# Fathom_Drone_Pi_Shield.net
KiCad netlist of a schematic drawn in EAGLE
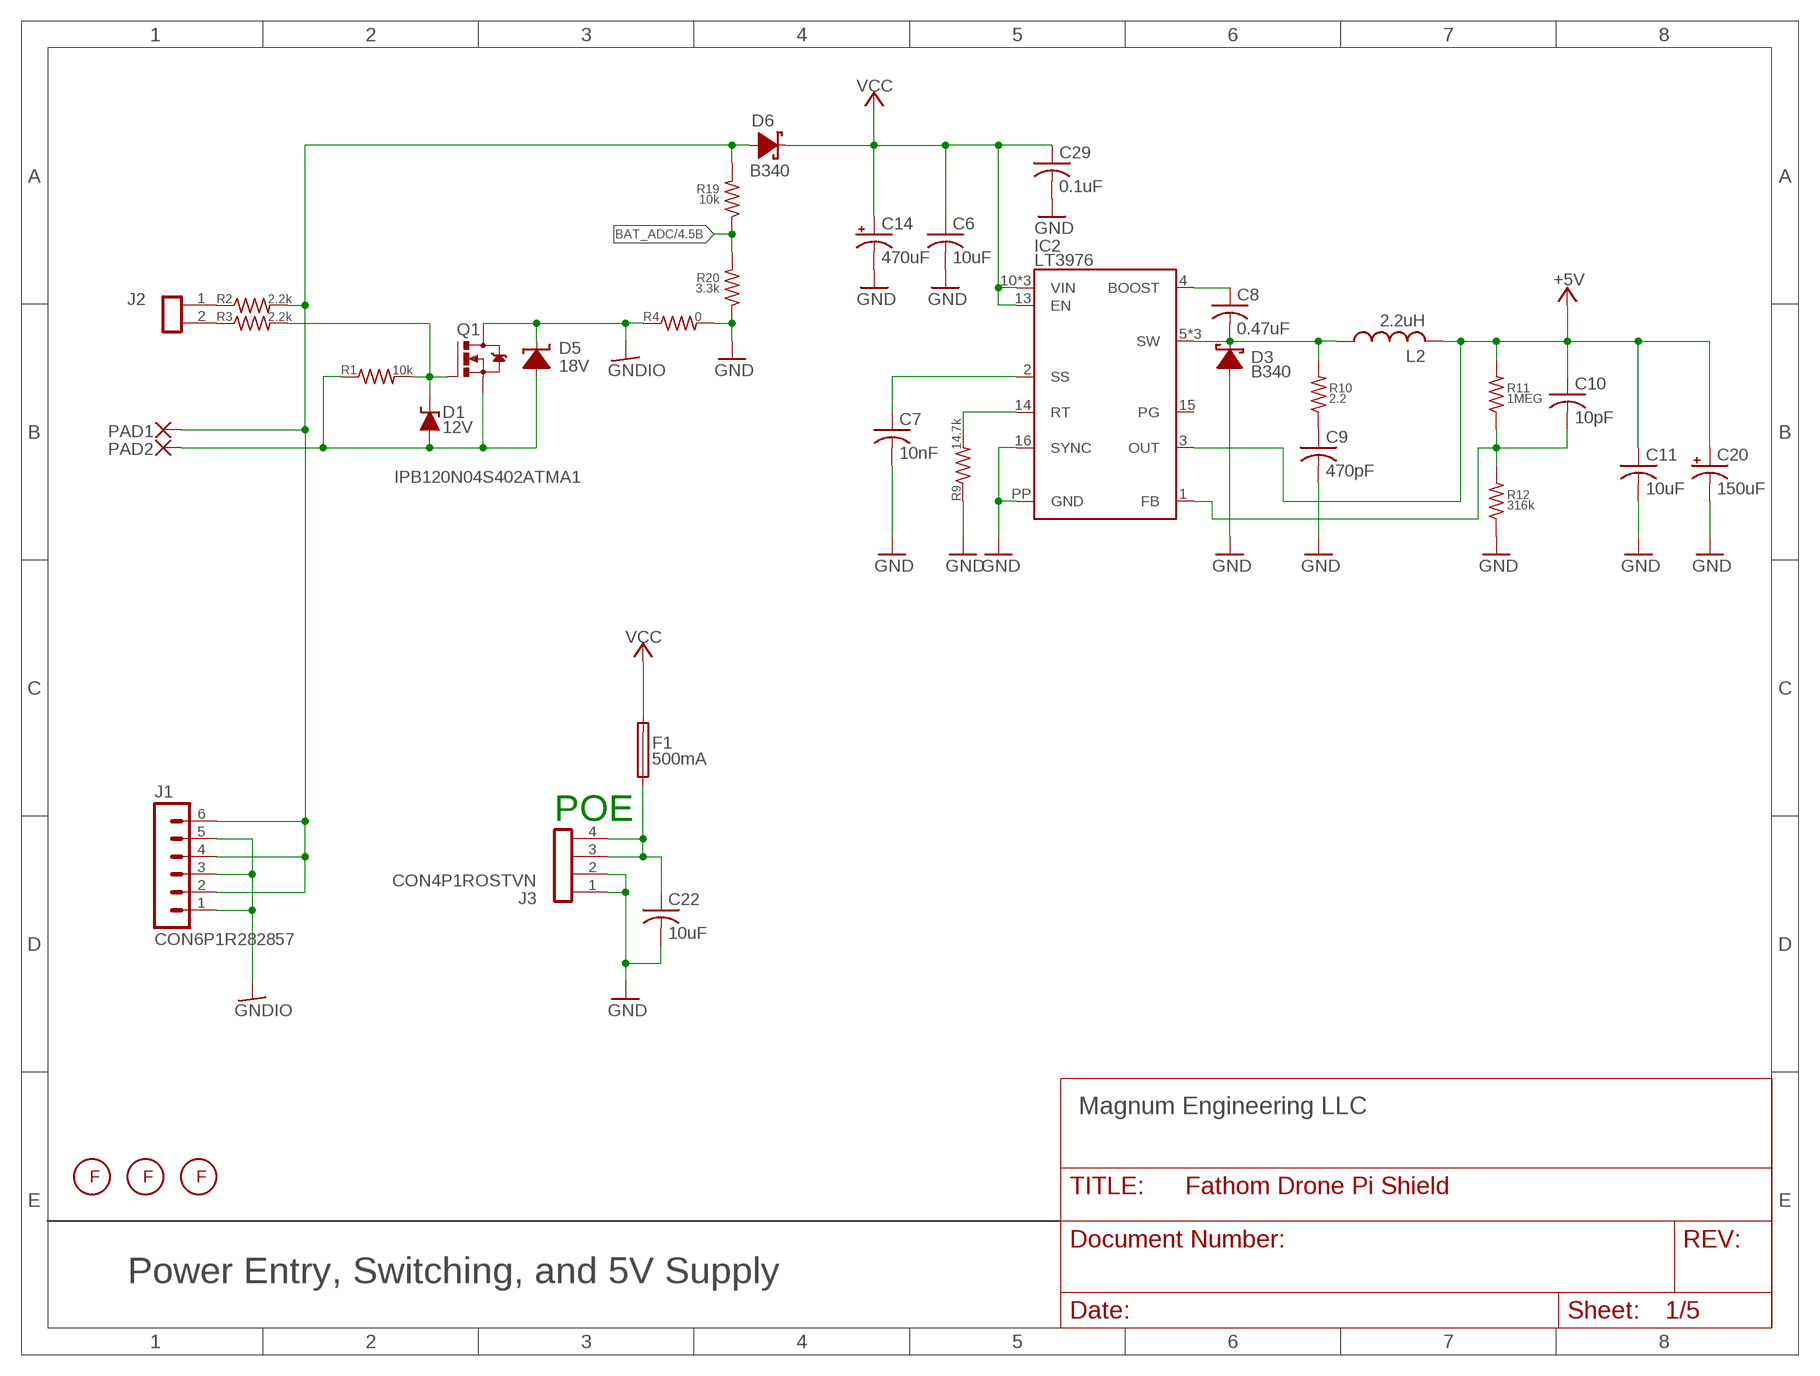
[diagram p0: schematic, sheet 1]
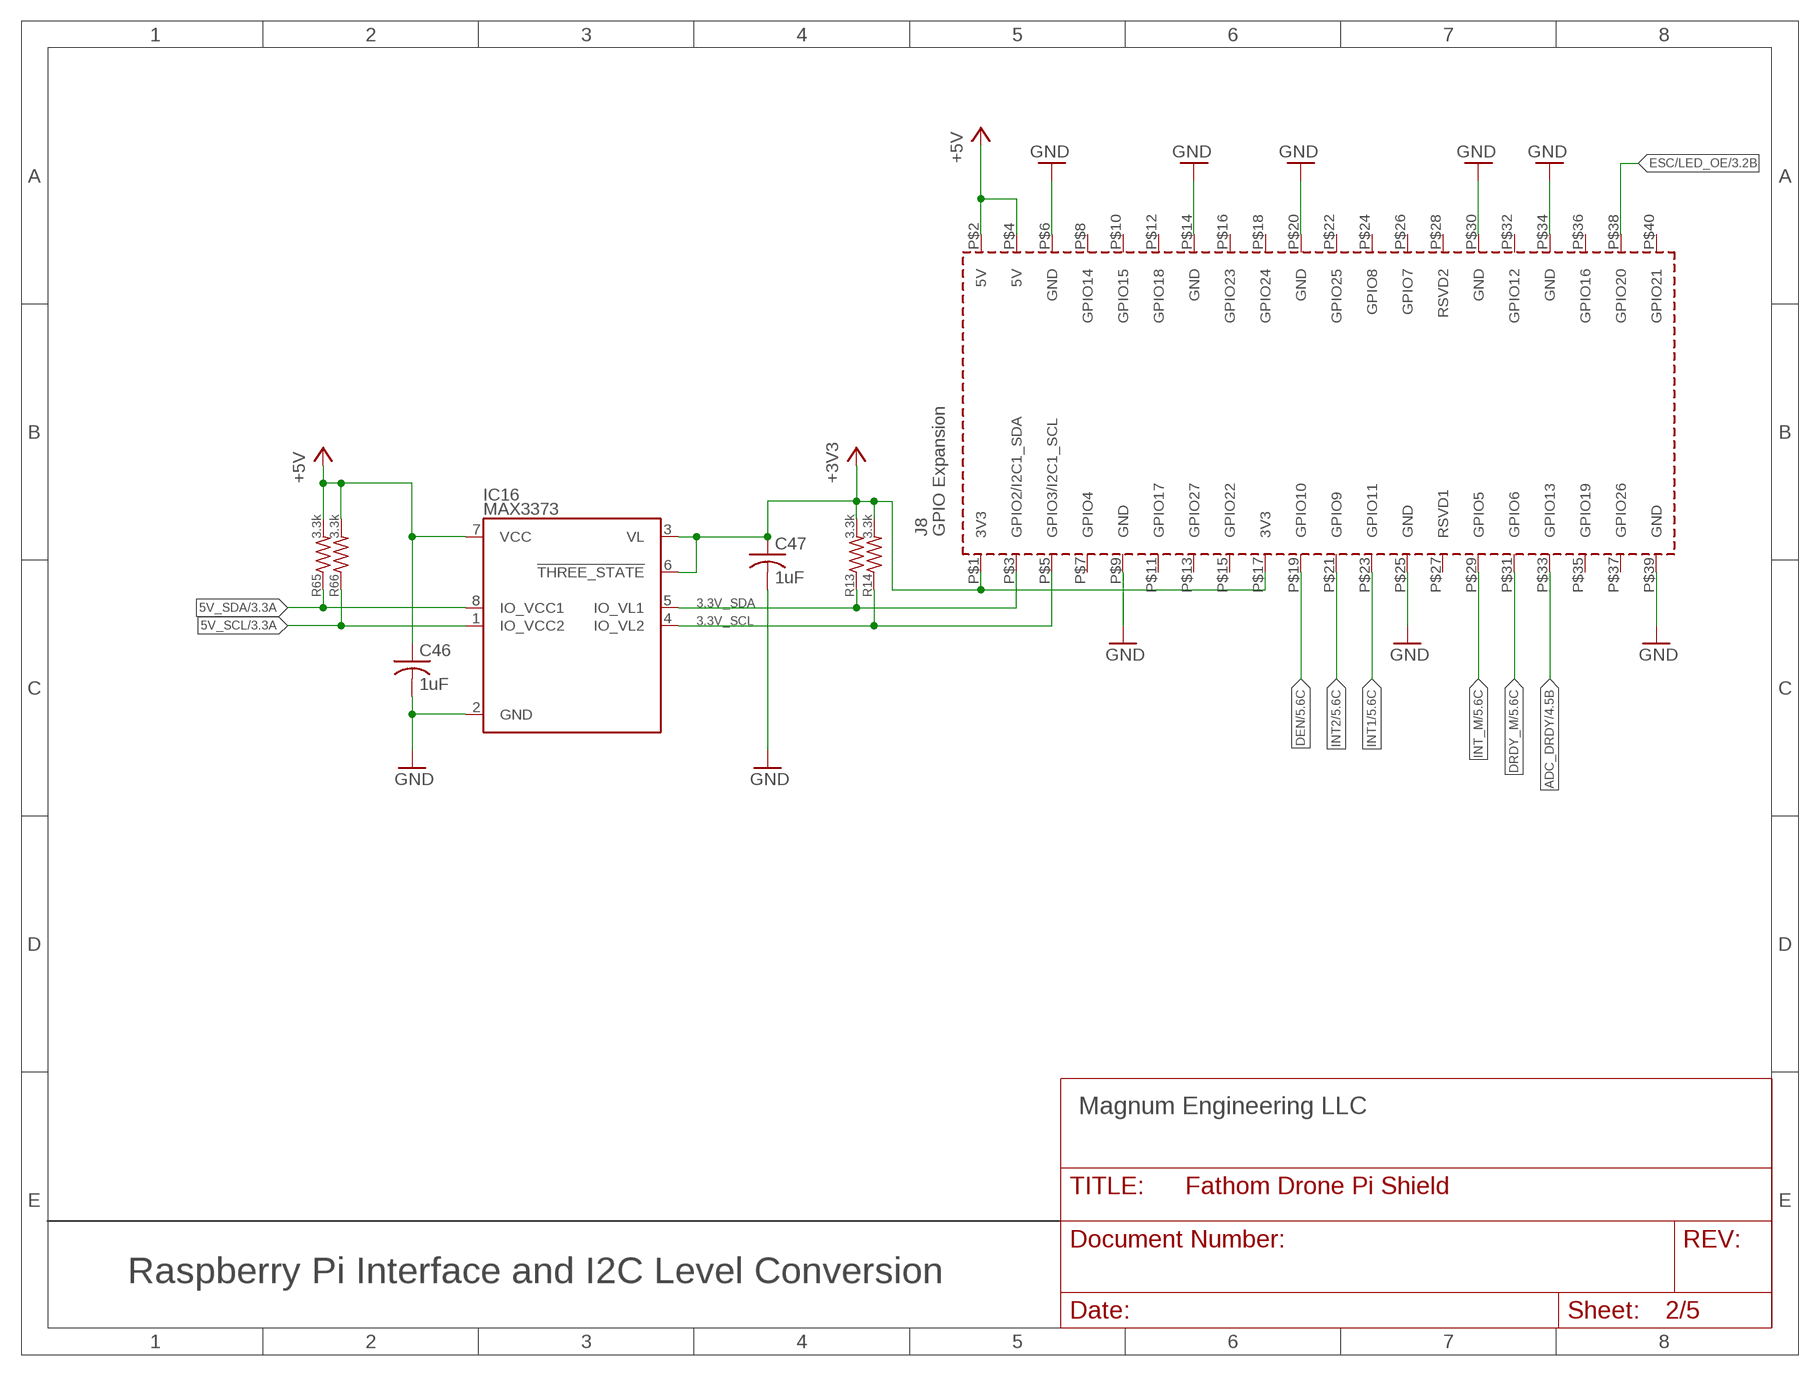
[diagram p1: schematic, sheet 2]
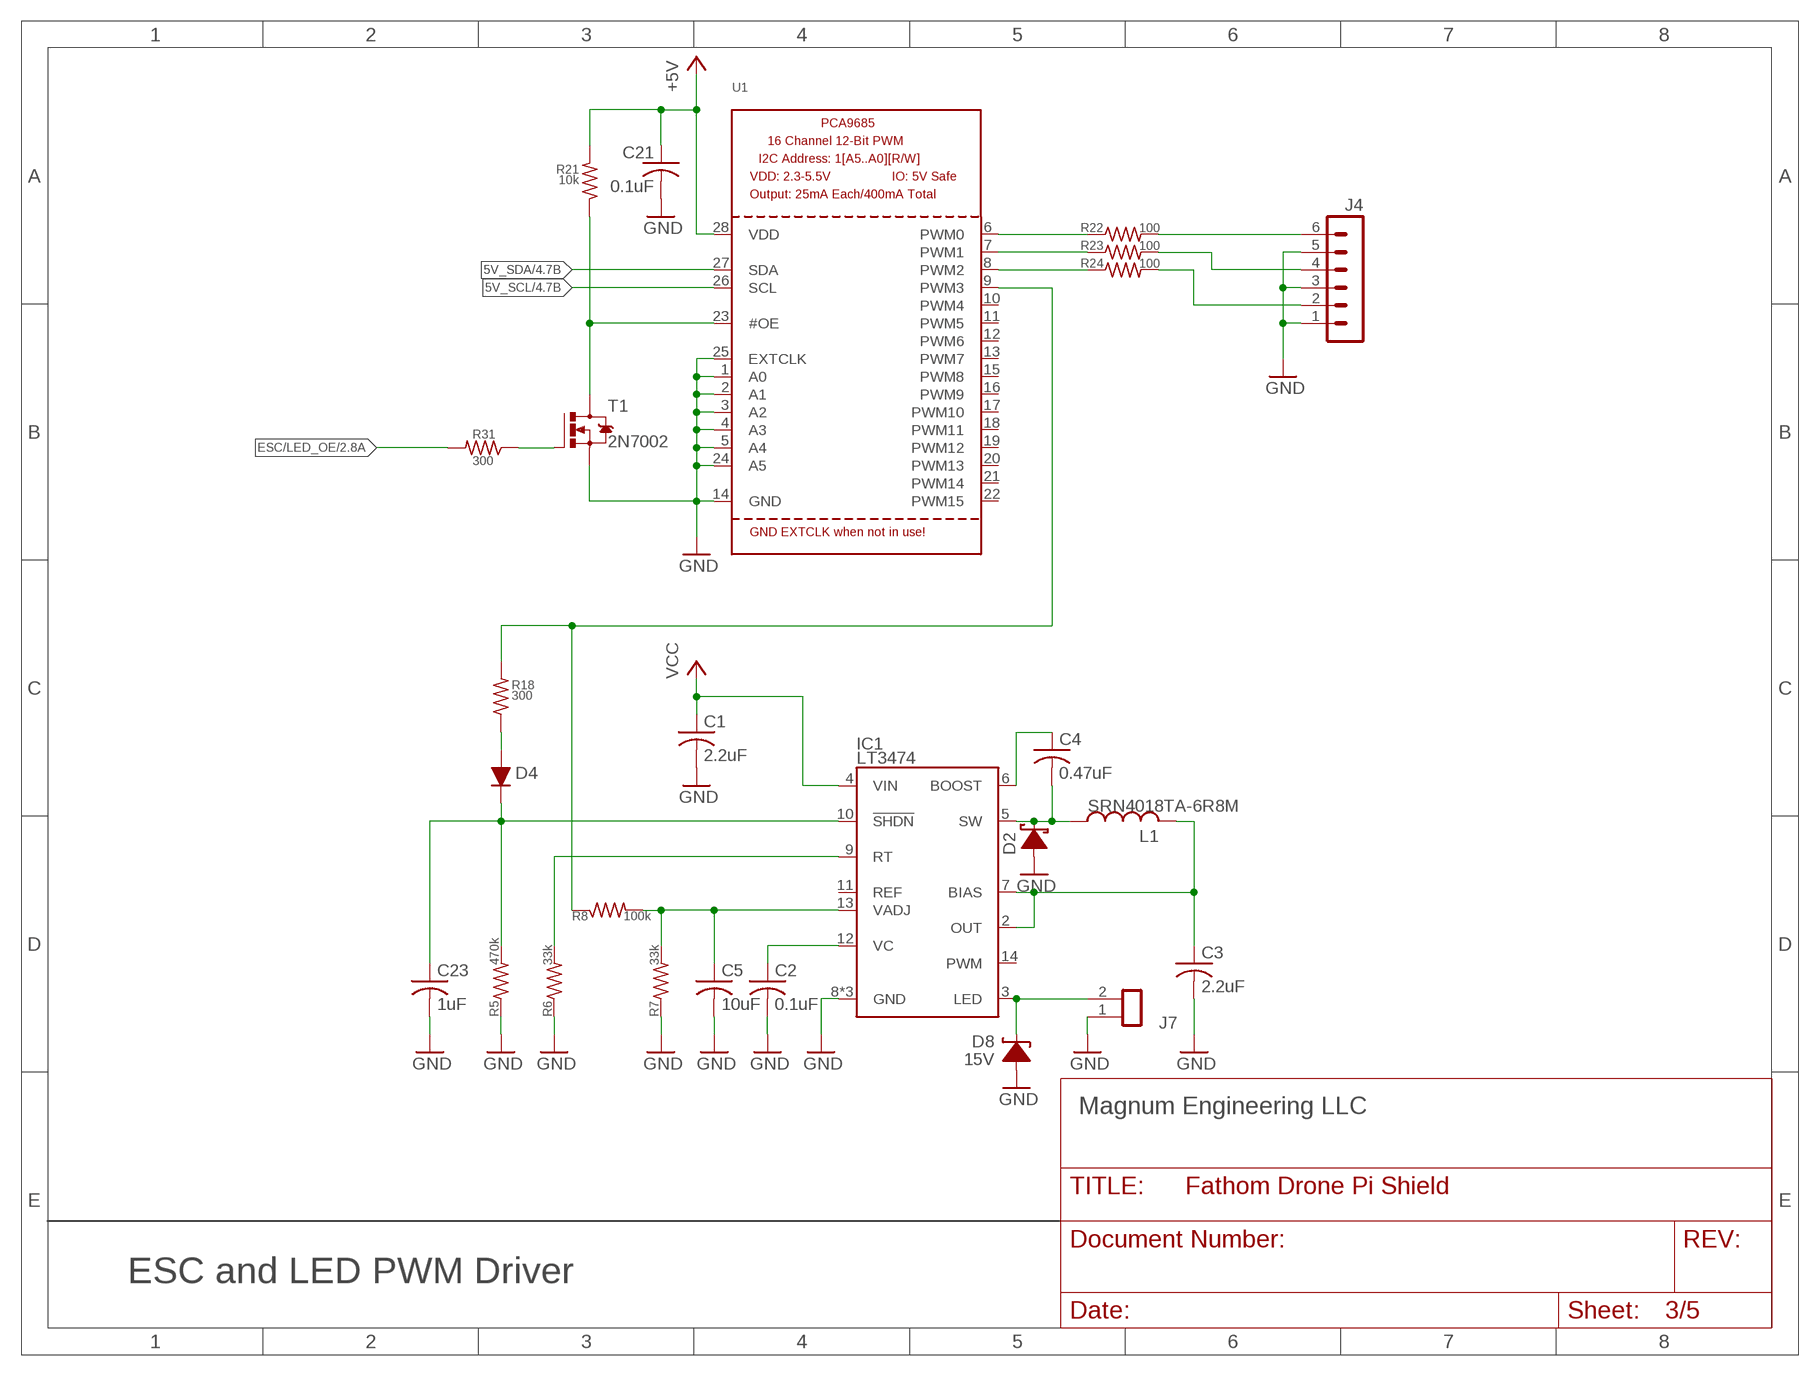
[diagram p2: schematic, sheet 3]
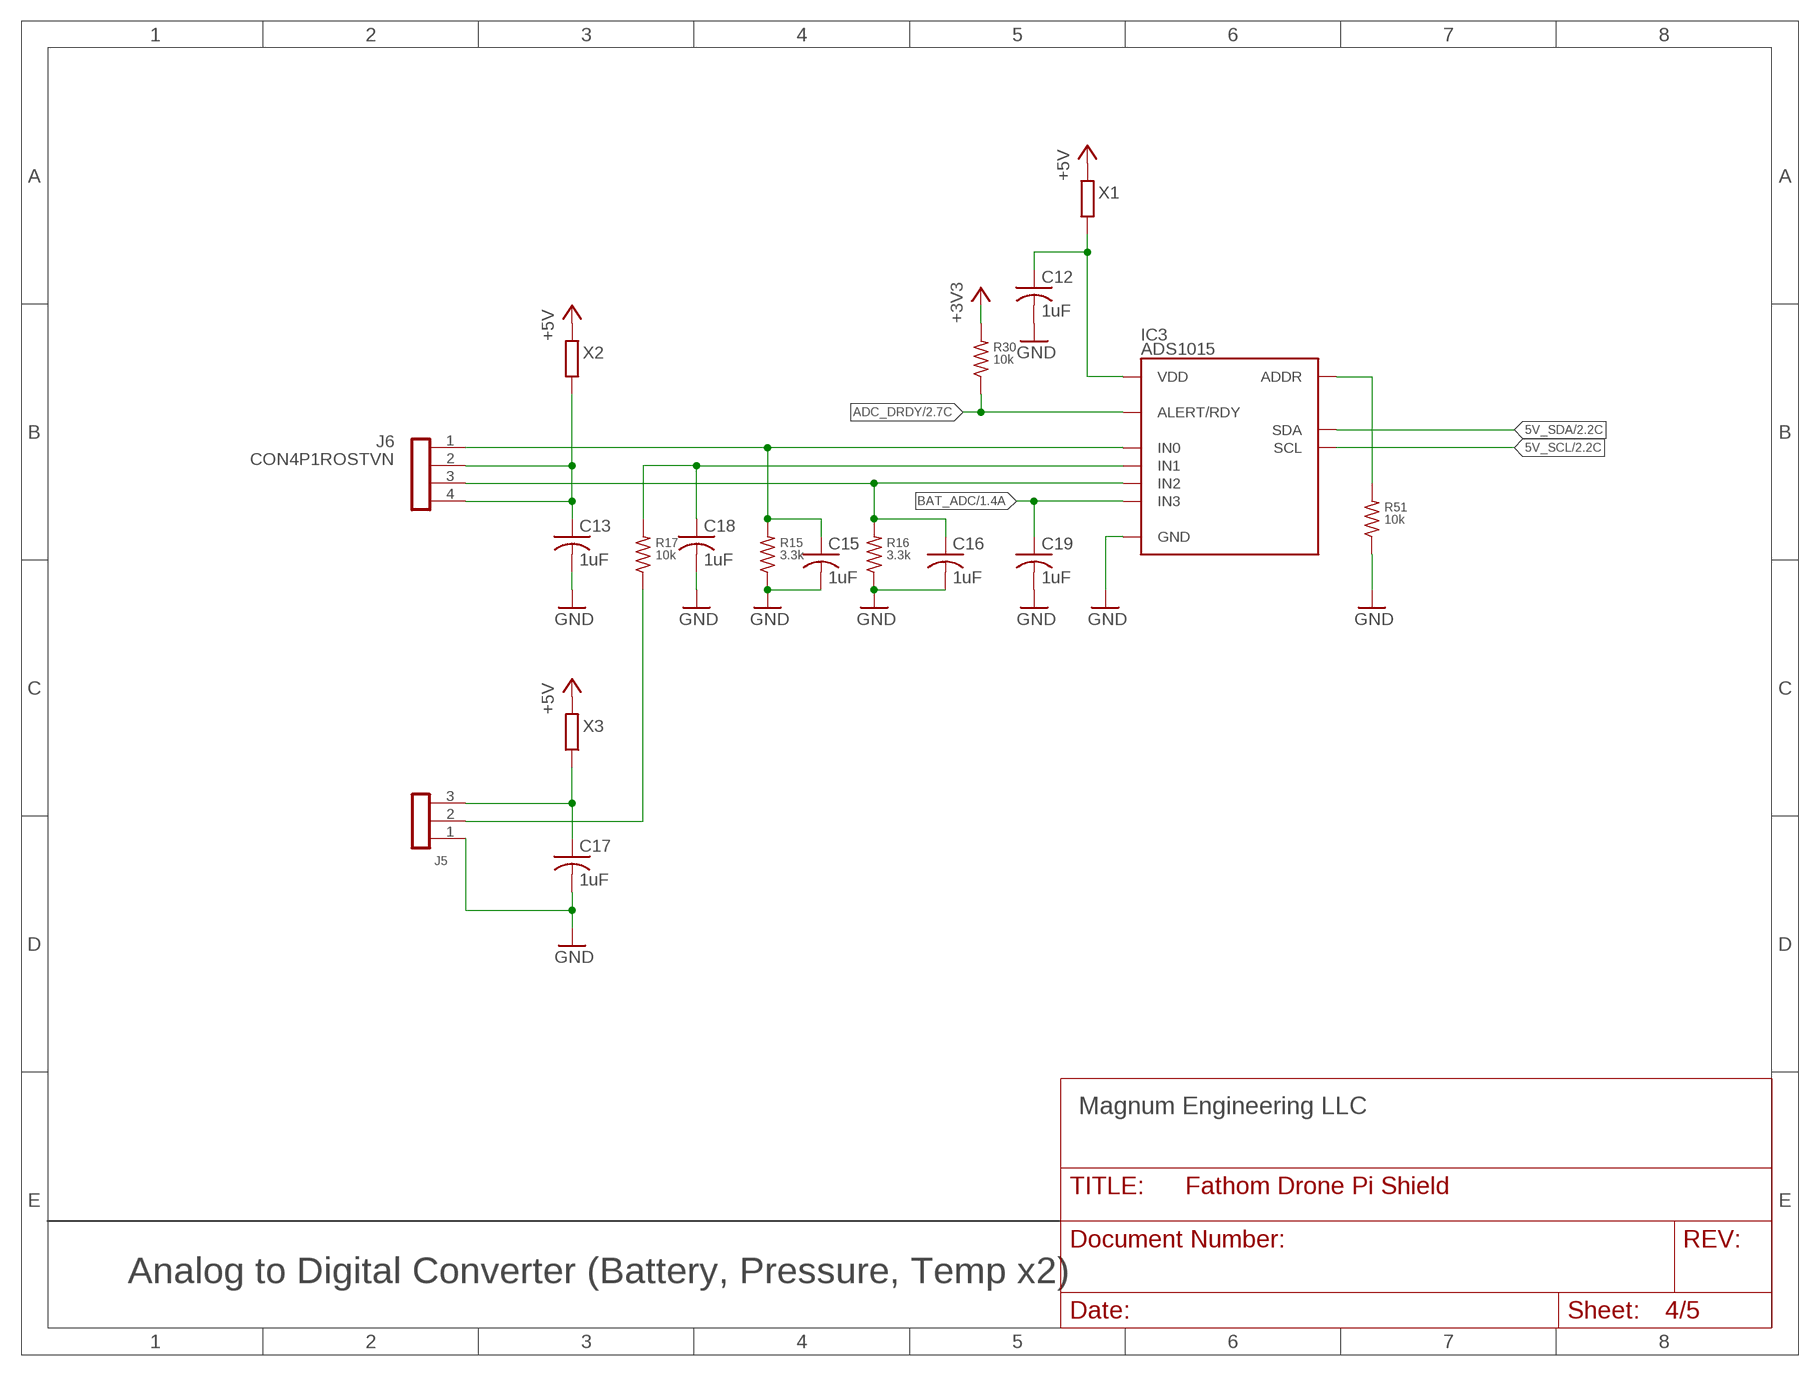
[diagram p3: schematic, sheet 4]
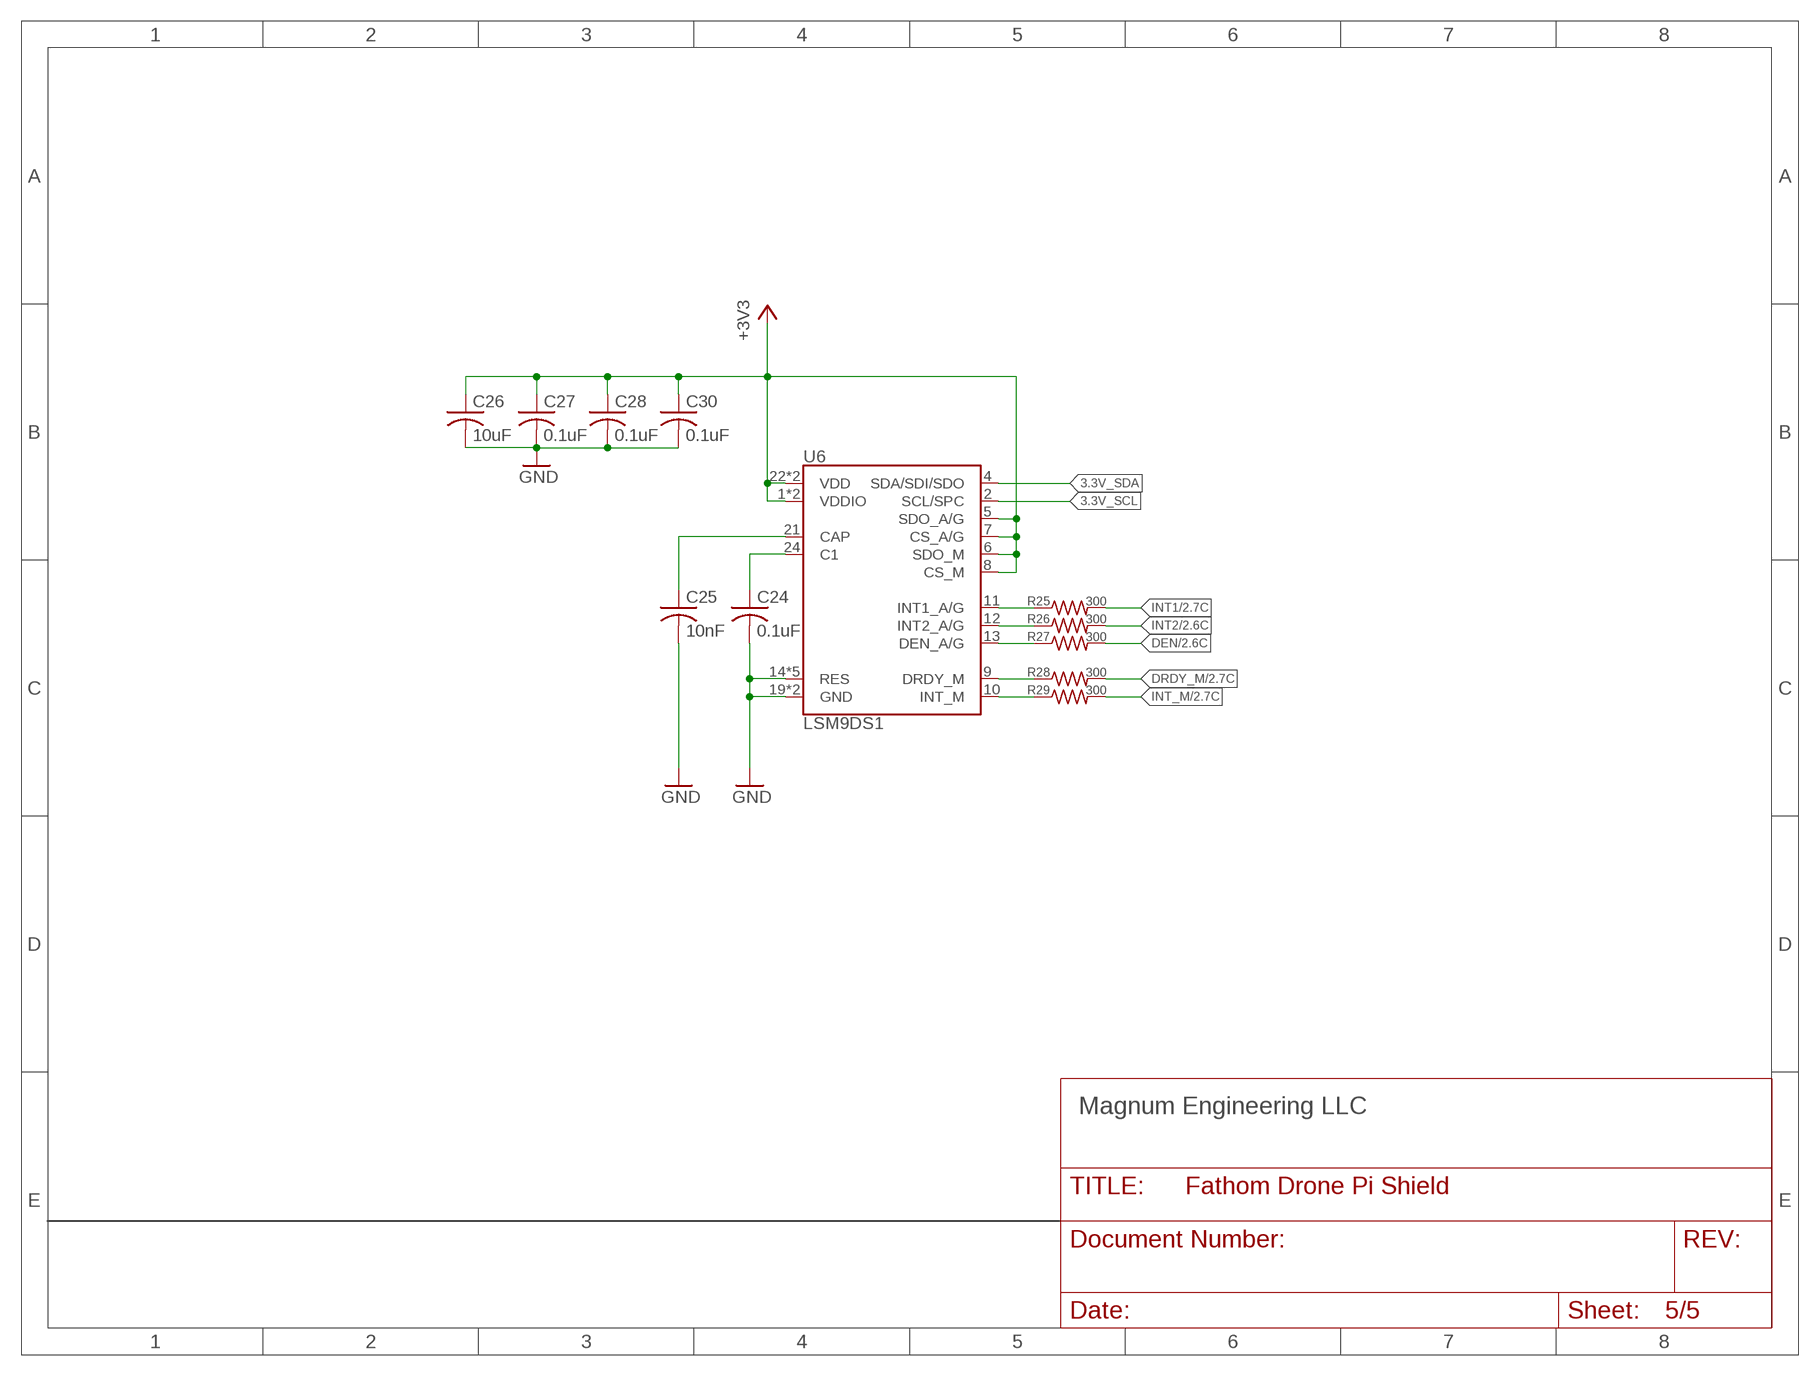
[diagram p4: schematic, sheet 5]

(export (version "E")
  (design (tool "Eeschema 10.0.6"))
  (components
    (comp (ref "C24")
      (value "0.1uF")
      (footprint "eagle-import:C0402")
      (libsource (lib "eagle-import") (part "CAPACITOR0402"))
    )
    (comp (ref "C25")
      (value "10nF")
      (footprint "eagle-import:C0402")
      (libsource (lib "eagle-import") (part "CAPACITOR0402"))
    )
    (comp (ref "C26")
      (value "10uF")
      (footprint "eagle-import:C0805")
      (libsource (lib "eagle-import") (part "CAPACITOR0805"))
    )
    (comp (ref "C27")
      (value "0.1uF")
      (footprint "eagle-import:C0402")
      (libsource (lib "eagle-import") (part "CAPACITOR0402"))
    )
    (comp (ref "C28")
      (value "0.1uF")
      (footprint "eagle-import:C0402")
      (libsource (lib "eagle-import") (part "CAPACITOR0402"))
    )
    (comp (ref "C30")
      (value "0.1uF")
      (footprint "eagle-import:C0402")
      (libsource (lib "eagle-import") (part "CAPACITOR0402"))
    )
    (comp (ref "R25")
      (value "300")
      (footprint "eagle-import:R0402")
      (libsource (lib "eagle-import") (part "RESISTOR0402"))
    )
    (comp (ref "R26")
      (value "300")
      (footprint "eagle-import:R0402")
      (libsource (lib "eagle-import") (part "RESISTOR0402"))
    )
    (comp (ref "R27")
      (value "300")
      (footprint "eagle-import:R0402")
      (libsource (lib "eagle-import") (part "RESISTOR0402"))
    )
    (comp (ref "R28")
      (value "300")
      (footprint "eagle-import:R0402")
      (libsource (lib "eagle-import") (part "RESISTOR0402"))
    )
    (comp (ref "R29")
      (value "300")
      (footprint "eagle-import:R0402")
      (libsource (lib "eagle-import") (part "RESISTOR0402"))
    )
    (comp (ref "U6")
      (value "LSM9DS1")
      (footprint "eagle-import:LGA24-8X4")
      (libsource (lib "eagle-import") (part "LSM9DS1"))
    )
    (comp (ref "C12")
      (value "1uF")
      (footprint "eagle-import:C0402")
      (libsource (lib "eagle-import") (part "CAPACITOR0402"))
    )
    (comp (ref "C13")
      (value "1uF")
      (footprint "eagle-import:C0402")
      (libsource (lib "eagle-import") (part "CAPACITOR0402"))
    )
    (comp (ref "C15")
      (value "1uF")
      (footprint "eagle-import:C0402")
      (libsource (lib "eagle-import") (part "CAPACITOR0402"))
    )
    (comp (ref "C16")
      (value "1uF")
      (footprint "eagle-import:C0402")
      (libsource (lib "eagle-import") (part "CAPACITOR0402"))
    )
    (comp (ref "C17")
      (value "1uF")
      (footprint "eagle-import:C0402")
      (libsource (lib "eagle-import") (part "CAPACITOR0402"))
    )
    (comp (ref "C18")
      (value "1uF")
      (footprint "eagle-import:C0402")
      (libsource (lib "eagle-import") (part "CAPACITOR0402"))
    )
    (comp (ref "C19")
      (value "1uF")
      (footprint "eagle-import:C0402")
      (libsource (lib "eagle-import") (part "CAPACITOR0402"))
    )
    (comp (ref "IC3")
      (value "ADS1015")
      (footprint "eagle-import:MSOP10")
      (libsource (lib "eagle-import") (part "ADS1015"))
    )
    (comp (ref "J5")
      (value "CON3P1ROSTVN")
      (footprint "eagle-import:OSTVN03A150")
      (libsource (lib "eagle-import") (part "CON3P1ROSTVN"))
    )
    (comp (ref "J6")
      (value "CON4P1ROSTVN")
      (footprint "eagle-import:OSTVN04A150")
      (libsource (lib "eagle-import") (part "CON4P1ROSTVN"))
    )
    (comp (ref "R15")
      (value "3.3k")
      (footprint "eagle-import:R0402")
      (libsource (lib "eagle-import") (part "RESISTOR0402"))
    )
    (comp (ref "R16")
      (value "3.3k")
      (footprint "eagle-import:R0402")
      (libsource (lib "eagle-import") (part "RESISTOR0402"))
    )
    (comp (ref "R17")
      (value "10k")
      (footprint "eagle-import:R0603")
      (libsource (lib "eagle-import") (part "RESISTOR0603"))
    )
    (comp (ref "R30")
      (value "10k")
      (footprint "eagle-import:R0603")
      (libsource (lib "eagle-import") (part "RESISTOR0603"))
    )
    (comp (ref "R51")
      (value "10k")
      (footprint "eagle-import:R0603")
      (libsource (lib "eagle-import") (part "RESISTOR0603"))
    )
    (comp (ref "X1")
      (value "PASSIVE0603")
      (footprint "eagle-import:R0603@1")
      (libsource (lib "eagle-import") (part "PASSIVE0603"))
    )
    (comp (ref "X2")
      (value "PASSIVE0603")
      (footprint "eagle-import:R0603@1")
      (libsource (lib "eagle-import") (part "PASSIVE0603"))
    )
    (comp (ref "X3")
      (value "PASSIVE0603")
      (footprint "eagle-import:R0603@1")
      (libsource (lib "eagle-import") (part "PASSIVE0603"))
    )
    (comp (ref "C46")
      (value "1uF")
      (footprint "eagle-import:C0402")
      (libsource (lib "eagle-import") (part "CAPACITOR0402"))
    )
    (comp (ref "C47")
      (value "1uF")
      (footprint "eagle-import:C0402")
      (libsource (lib "eagle-import") (part "CAPACITOR0402"))
    )
    (comp (ref "IC16")
      (value "MAX3373")
      (footprint "eagle-import:TS8")
      (libsource (lib "eagle-import") (part "MAX3373"))
    )
    (comp (ref "PCB1")
      (value "RPI3")
      (footprint "eagle-import:RPI3")
      (libsource (lib "eagle-import") (part "RPI3"))
    )
    (comp (ref "R13")
      (value "3.3k")
      (footprint "eagle-import:R0402")
      (libsource (lib "eagle-import") (part "RESISTOR0402"))
    )
    (comp (ref "R14")
      (value "3.3k")
      (footprint "eagle-import:R0402")
      (libsource (lib "eagle-import") (part "RESISTOR0402"))
    )
    (comp (ref "R65")
      (value "3.3k")
      (footprint "eagle-import:R0402")
      (libsource (lib "eagle-import") (part "RESISTOR0402"))
    )
    (comp (ref "R66")
      (value "3.3k")
      (footprint "eagle-import:R0402")
      (libsource (lib "eagle-import") (part "RESISTOR0402"))
    )
    (comp (ref "C6")
      (value "10uF")
      (footprint "eagle-import:C1206")
      (libsource (lib "eagle-import") (part "C-USC1206"))
    )
    (comp (ref "C7")
      (value "10nF")
      (footprint "eagle-import:C0402")
      (libsource (lib "eagle-import") (part "CAPACITOR0402"))
    )
    (comp (ref "C8")
      (value "0.47uF")
      (footprint "eagle-import:C0603")
      (libsource (lib "eagle-import") (part "CAPACITOR0603"))
    )
    (comp (ref "C9")
      (value "470pF")
      (footprint "eagle-import:C0603")
      (libsource (lib "eagle-import") (part "CAPACITOR0603"))
    )
    (comp (ref "C10")
      (value "10pF")
      (footprint "eagle-import:C0603")
      (libsource (lib "eagle-import") (part "CAPACITOR0603"))
    )
    (comp (ref "C11")
      (value "10uF")
      (footprint "eagle-import:C0805")
      (libsource (lib "eagle-import") (part "CAPACITOR0805"))
    )
    (comp (ref "C14")
      (value "470uF")
      (footprint "eagle-import:E3,5-8")
      (libsource (lib "eagle-import") (part "CPOL-USE3.5-8"))
    )
    (comp (ref "C20")
      (value "150uF")
      (footprint "eagle-import:PANASONIC_C")
      (libsource (lib "eagle-import") (part "CPOL-USC"))
    )
    (comp (ref "C22")
      (value "10uF")
      (footprint "eagle-import:C1206")
      (libsource (lib "eagle-import") (part "C-USC1206"))
    )
    (comp (ref "C29")
      (value "0.1uF")
      (footprint "eagle-import:C0402")
      (libsource (lib "eagle-import") (part "C-USC0402"))
    )
    (comp (ref "D1")
      (value "12V")
      (footprint "eagle-import:SOT-23")
      (libsource (lib "eagle-import") (part "ZENERSOT-23"))
    )
    (comp (ref "D3")
      (value "B340")
      (footprint "eagle-import:SMA")
      (libsource (lib "eagle-import") (part "DIODE-SCHOTTKYSMA"))
    )
    (comp (ref "D5")
      (value "18V")
      (footprint "eagle-import:SMC")
      (libsource (lib "eagle-import") (part "TVSSMC"))
    )
    (comp (ref "D6")
      (value "B340")
      (footprint "eagle-import:SMA")
      (libsource (lib "eagle-import") (part "DIODE-SCHOTTKYSMA"))
    )
    (comp (ref "F1")
      (value "500mA")
      (footprint "eagle-import:BETTER_LITTELFUSE1812")
      (libsource (lib "eagle-import") (part "FUSEBETTER_1812"))
    )
    (comp (ref "FM1")
      (value "FIDUCIAL1MM")
      (footprint "eagle-import:1MMCIRCLE")
      (libsource (lib "eagle-import") (part "FIDUCIAL1MM"))
    )
    (comp (ref "FM2")
      (value "FIDUCIAL1MM")
      (footprint "eagle-import:1MMCIRCLE")
      (libsource (lib "eagle-import") (part "FIDUCIAL1MM"))
    )
    (comp (ref "FM3")
      (value "FIDUCIAL1MM")
      (footprint "eagle-import:1MMCIRCLE")
      (libsource (lib "eagle-import") (part "FIDUCIAL1MM"))
    )
    (comp (ref "IC2")
      (value "LT3976")
      (footprint "eagle-import:MSOP-16-PP")
      (libsource (lib "eagle-import") (part "LT3976"))
    )
    (comp (ref "J1")
      (value "CON6P1R282857")
      (footprint "eagle-import:282857-6")
      (libsource (lib "eagle-import") (part "CON6P1R282857"))
    )
    (comp (ref "J2")
      (value "CON2P1ROSTVN")
      (footprint "eagle-import:OSTVN02A150")
      (libsource (lib "eagle-import") (part "CON2P1ROSTVN"))
    )
    (comp (ref "J3")
      (value "CON4P1ROSTVN")
      (footprint "eagle-import:OSTVN04A150")
      (libsource (lib "eagle-import") (part "CON4P1ROSTVN"))
    )
    (comp (ref "L2")
      (value "2.2uH")
      (footprint "eagle-import:VLP8040")
      (libsource (lib "eagle-import") (part "L-USVLP8040"))
    )
    (comp (ref "PAD1")
      (value "WIREPAD5.5/3,0")
      (footprint "eagle-import:5.5_3,0")
      (libsource (lib "eagle-import") (part "WIREPAD5.5/3,0"))
    )
    (comp (ref "PAD2")
      (value "WIREPAD5.5/3,0")
      (footprint "eagle-import:5.5_3,0")
      (libsource (lib "eagle-import") (part "WIREPAD5.5/3,0"))
    )
    (comp (ref "Q1")
      (value "IPB120N04S402ATMA1")
      (footprint "eagle-import:TO263")
      (libsource (lib "eagle-import") (part "MOSFET-NTO263"))
    )
    (comp (ref "R1")
      (value "10k")
      (footprint "eagle-import:R0603")
      (libsource (lib "eagle-import") (part "RESISTOR0603"))
    )
    (comp (ref "R2")
      (value "2.2k")
      (footprint "eagle-import:R0603")
      (libsource (lib "eagle-import") (part "RESISTOR0603"))
    )
    (comp (ref "R3")
      (value "2.2k")
      (footprint "eagle-import:R0603")
      (libsource (lib "eagle-import") (part "RESISTOR0603"))
    )
    (comp (ref "R4")
      (value "0")
      (footprint "eagle-import:R0805")
      (libsource (lib "eagle-import") (part "RESISTOR0805"))
    )
    (comp (ref "R9")
      (value "14.7k")
      (footprint "eagle-import:R0603")
      (libsource (lib "eagle-import") (part "RESISTOR0603"))
    )
    (comp (ref "R10")
      (value "2.2")
      (footprint "eagle-import:R0603")
      (libsource (lib "eagle-import") (part "RESISTOR0603"))
    )
    (comp (ref "R11")
      (value "1MEG")
      (footprint "eagle-import:R0603")
      (libsource (lib "eagle-import") (part "RESISTOR0603"))
    )
    (comp (ref "R12")
      (value "316k")
      (footprint "eagle-import:R0603")
      (libsource (lib "eagle-import") (part "RESISTOR0603"))
    )
    (comp (ref "R19")
      (value "10k")
      (footprint "eagle-import:R0603")
      (libsource (lib "eagle-import") (part "RESISTOR0603"))
    )
    (comp (ref "R20")
      (value "3.3k")
      (footprint "eagle-import:R0402")
      (libsource (lib "eagle-import") (part "RESISTOR0402"))
    )
    (comp (ref "C1")
      (value "2.2uF")
      (footprint "eagle-import:C0603")
      (libsource (lib "eagle-import") (part "CAPACITOR0603"))
    )
    (comp (ref "C2")
      (value "0.1uF")
      (footprint "eagle-import:C0402")
      (libsource (lib "eagle-import") (part "CAPACITOR0402"))
    )
    (comp (ref "C3")
      (value "2.2uF")
      (footprint "eagle-import:C0603")
      (libsource (lib "eagle-import") (part "CAPACITOR0603"))
    )
    (comp (ref "C4")
      (value "0.47uF")
      (footprint "eagle-import:C0603")
      (libsource (lib "eagle-import") (part "CAPACITOR0603"))
    )
    (comp (ref "C5")
      (value "10uF")
      (footprint "eagle-import:C0805")
      (libsource (lib "eagle-import") (part "CAPACITOR0805"))
    )
    (comp (ref "C21")
      (value "0.1uF")
      (footprint "eagle-import:C0402")
      (libsource (lib "eagle-import") (part "CAPACITOR0402"))
    )
    (comp (ref "C23")
      (value "1uF")
      (footprint "eagle-import:C0402")
      (libsource (lib "eagle-import") (part "CAPACITOR0402"))
    )
    (comp (ref "D2")
      (value "DIODE-SCHOTTKYSMA")
      (footprint "eagle-import:SMA")
      (libsource (lib "eagle-import") (part "DIODE-SCHOTTKYSMA"))
    )
    (comp (ref "D4")
      (value "DIODESOD-123")
      (footprint "eagle-import:SOD-123")
      (libsource (lib "eagle-import") (part "DIODESOD-123"))
    )
    (comp (ref "D8")
      (value "15V")
      (footprint "eagle-import:SOD123FL")
      (libsource (lib "eagle-import") (part "TVSSOD123FL"))
    )
    (comp (ref "IC1")
      (value "LT3474")
      (footprint "eagle-import:TSSOP16_PP")
      (libsource (lib "eagle-import") (part "LT3474"))
    )
    (comp (ref "J4")
      (value "CON6P1ROSTVN")
      (footprint "eagle-import:OSTVN06A150")
      (libsource (lib "eagle-import") (part "CON6P1ROSTVN"))
    )
    (comp (ref "J7")
      (value "CON2P1ROSTVN")
      (footprint "eagle-import:OSTVN02A150")
      (libsource (lib "eagle-import") (part "CON2P1ROSTVN"))
    )
    (comp (ref "L1")
      (value "SRN4018TA-6R8M")
      (footprint "eagle-import:L-4026")
      (libsource (lib "eagle-import") (part "L-US4026"))
    )
    (comp (ref "R5")
      (value "470k")
      (footprint "eagle-import:R0603")
      (libsource (lib "eagle-import") (part "RESISTOR0603"))
    )
    (comp (ref "R6")
      (value "33k")
      (footprint "eagle-import:R0603")
      (libsource (lib "eagle-import") (part "RESISTOR0603"))
    )
    (comp (ref "R7")
      (value "33k")
      (footprint "eagle-import:R0603")
      (libsource (lib "eagle-import") (part "RESISTOR0603"))
    )
    (comp (ref "R8")
      (value "100k")
      (footprint "eagle-import:R0603")
      (libsource (lib "eagle-import") (part "RESISTOR0603"))
    )
    (comp (ref "R18")
      (value "300")
      (footprint "eagle-import:R0402")
      (libsource (lib "eagle-import") (part "RESISTOR0402"))
    )
    (comp (ref "R21")
      (value "10k")
      (footprint "eagle-import:R0603")
      (libsource (lib "eagle-import") (part "RESISTOR0603"))
    )
    (comp (ref "R22")
      (value "100")
      (footprint "eagle-import:R0603")
      (libsource (lib "eagle-import") (part "RESISTOR0603"))
    )
    (comp (ref "R23")
      (value "100")
      (footprint "eagle-import:R0603")
      (libsource (lib "eagle-import") (part "RESISTOR0603"))
    )
    (comp (ref "R24")
      (value "100")
      (footprint "eagle-import:R0603")
      (libsource (lib "eagle-import") (part "RESISTOR0603"))
    )
    (comp (ref "R31")
      (value "300")
      (footprint "eagle-import:R0402")
      (libsource (lib "eagle-import") (part "RESISTOR0402"))
    )
    (comp (ref "T1")
      (value "2N7002")
      (footprint "eagle-import:SOT-23")
      (libsource (lib "eagle-import") (part "N-MOSFET"))
    )
    (comp (ref "U1")
      (value "PCA9685")
      (footprint "eagle-import:TSSOP28")
      (libsource (lib "eagle-import") (part "PCA9685"))
    )
  )
  (nets
    (net (code "1") (name "+3V3") (class "Default")
      (node (ref "C26") (pin "1") (pinfunction "1_1") (pintype "passive"))
      (node (ref "C27") (pin "1") (pinfunction "1_1") (pintype "passive"))
      (node (ref "C28") (pin "1") (pinfunction "1_1") (pintype "passive"))
      (node (ref "C30") (pin "1") (pinfunction "1_1") (pintype "passive"))
      (node (ref "C47") (pin "1") (pinfunction "1_1") (pintype "passive"))
      (node (ref "IC16") (pin "3") (pinfunction "VL_3") (pintype "power_in"))
      (node (ref "IC16") (pin "6") (pinfunction "~{THREE_STATE}_6") (pintype "input"))
      (node (ref "PCB1") (pin "P$1") (pinfunction "3V3_P$1") (pintype "bidirectional"))
      (node (ref "PCB1") (pin "P$17") (pinfunction "3V3_P$17") (pintype "bidirectional"))
      (node (ref "R13") (pin "2") (pinfunction "2_2") (pintype "passive"))
      (node (ref "R14") (pin "2") (pinfunction "2_2") (pintype "passive"))
      (node (ref "R30") (pin "2") (pinfunction "2_2") (pintype "passive"))
      (node (ref "U6") (pin "1") (pinfunction "VDDIO_1") (pintype "bidirectional"))
      (node (ref "U6") (pin "22") (pinfunction "VDD_22") (pintype "bidirectional"))
      (node (ref "U6") (pin "23") (pinfunction "VDD_23") (pintype "bidirectional"))
      (node (ref "U6") (pin "3") (pinfunction "VDDIO_3") (pintype "bidirectional"))
      (node (ref "U6") (pin "5") (pinfunction "SDO_A/G_5") (pintype "bidirectional"))
      (node (ref "U6") (pin "6") (pinfunction "SDO_M_6") (pintype "bidirectional"))
      (node (ref "U6") (pin "7") (pinfunction "CS_A/G_7") (pintype "bidirectional"))
      (node (ref "U6") (pin "8") (pinfunction "CS_M_8") (pintype "bidirectional"))
    )
    (net (code "2") (name "+5V") (class "Default")
      (node (ref "C10") (pin "1") (pinfunction "1_1") (pintype "passive"))
      (node (ref "C11") (pin "1") (pinfunction "1_1") (pintype "passive"))
      (node (ref "C20") (pin "+") (pinfunction "+_+") (pintype "passive"))
      (node (ref "C21") (pin "1") (pinfunction "1_1") (pintype "passive"))
      (node (ref "C46") (pin "1") (pinfunction "1_1") (pintype "passive"))
      (node (ref "IC16") (pin "7") (pinfunction "VCC_7") (pintype "power_in"))
      (node (ref "IC2") (pin "3") (pinfunction "OUT_3") (pintype "input"))
      (node (ref "L2") (pin "P$2") (pinfunction "2_P$2") (pintype "passive"))
      (node (ref "PCB1") (pin "P$2") (pinfunction "5V_P$2") (pintype "bidirectional"))
      (node (ref "PCB1") (pin "P$4") (pinfunction "5V_P$4") (pintype "bidirectional"))
      (node (ref "R11") (pin "2") (pinfunction "2_2") (pintype "passive"))
      (node (ref "R21") (pin "2") (pinfunction "2_2") (pintype "passive"))
      (node (ref "R65") (pin "2") (pinfunction "2_2") (pintype "passive"))
      (node (ref "R66") (pin "2") (pinfunction "2_2") (pintype "passive"))
      (node (ref "U1") (pin "28") (pinfunction "VDD_28") (pintype "power_in"))
      (node (ref "X1") (pin "2") (pinfunction "2_2") (pintype "passive"))
      (node (ref "X2") (pin "2") (pinfunction "2_2") (pintype "passive"))
      (node (ref "X3") (pin "2") (pinfunction "2_2") (pintype "passive"))
    )
    (net (code "3") (name "3.3V_SCL") (class "Default")
      (node (ref "IC16") (pin "4") (pinfunction "IO_VL2_4") (pintype "bidirectional"))
      (node (ref "PCB1") (pin "P$5") (pinfunction "GPIO3/I2C1_SCL_P$5") (pintype "bidirectional"))
      (node (ref "R14") (pin "1") (pinfunction "1_1") (pintype "passive"))
      (node (ref "U6") (pin "2") (pinfunction "SCL/SPC_2") (pintype "bidirectional"))
    )
    (net (code "4") (name "3.3V_SDA") (class "Default")
      (node (ref "IC16") (pin "5") (pinfunction "IO_VL1_5") (pintype "bidirectional"))
      (node (ref "PCB1") (pin "P$3") (pinfunction "GPIO2/I2C1_SDA_P$3") (pintype "bidirectional"))
      (node (ref "R13") (pin "1") (pinfunction "1_1") (pintype "passive"))
      (node (ref "U6") (pin "4") (pinfunction "SDA/SDI/SDO_4") (pintype "bidirectional"))
    )
    (net (code "5") (name "5V_SCL") (class "Default")
      (node (ref "IC16") (pin "1") (pinfunction "IO_VCC2_1") (pintype "bidirectional"))
      (node (ref "IC3") (pin "10") (pinfunction "SCL_10") (pintype "input"))
      (node (ref "R66") (pin "1") (pinfunction "1_1") (pintype "passive"))
      (node (ref "U1") (pin "26") (pinfunction "SCL_26") (pintype "bidirectional"))
    )
    (net (code "6") (name "5V_SDA") (class "Default")
      (node (ref "IC16") (pin "8") (pinfunction "IO_VCC1_8") (pintype "bidirectional"))
      (node (ref "IC3") (pin "9") (pinfunction "SDA_9") (pintype "bidirectional"))
      (node (ref "R65") (pin "1") (pinfunction "1_1") (pintype "passive"))
      (node (ref "U1") (pin "27") (pinfunction "SDA_27") (pintype "bidirectional"))
    )
    (net (code "7") (name "ADC_DRDY") (class "Default")
      (node (ref "IC3") (pin "2") (pinfunction "ALERT/RDY_2") (pintype "output"))
      (node (ref "PCB1") (pin "P$33") (pinfunction "GPIO13_P$33") (pintype "bidirectional"))
      (node (ref "R30") (pin "1") (pinfunction "1_1") (pintype "passive"))
    )
    (net (code "8") (name "BAT_ADC") (class "Default")
      (node (ref "C19") (pin "1") (pinfunction "1_1") (pintype "passive"))
      (node (ref "IC3") (pin "7") (pinfunction "IN3_7") (pintype "input"))
      (node (ref "R19") (pin "1") (pinfunction "1_1") (pintype "passive"))
      (node (ref "R20") (pin "2") (pinfunction "2_2") (pintype "passive"))
    )
    (net (code "9") (name "DEN") (class "Default")
      (node (ref "PCB1") (pin "P$19") (pinfunction "GPIO10_P$19") (pintype "bidirectional"))
      (node (ref "R27") (pin "2") (pinfunction "2_2") (pintype "passive"))
    )
    (net (code "10") (name "DRDY_M") (class "Default")
      (node (ref "PCB1") (pin "P$31") (pinfunction "GPIO6_P$31") (pintype "bidirectional"))
      (node (ref "R28") (pin "2") (pinfunction "2_2") (pintype "passive"))
    )
    (net (code "11") (name "ESC{slash}LED_OE") (class "Default")
      (node (ref "PCB1") (pin "P$38") (pinfunction "GPIO20_P$38") (pintype "bidirectional"))
      (node (ref "R31") (pin "2") (pinfunction "2_2") (pintype "passive"))
    )
    (net (code "12") (name "GND") (class "Default")
      (node (ref "C1") (pin "2") (pinfunction "2_2") (pintype "passive"))
      (node (ref "C11") (pin "2") (pinfunction "2_2") (pintype "passive"))
      (node (ref "C12") (pin "2") (pinfunction "2_2") (pintype "passive"))
      (node (ref "C13") (pin "2") (pinfunction "2_2") (pintype "passive"))
      (node (ref "C14") (pin "-") (pinfunction "-_-") (pintype "passive"))
      (node (ref "C15") (pin "2") (pinfunction "2_2") (pintype "passive"))
      (node (ref "C16") (pin "2") (pinfunction "2_2") (pintype "passive"))
      (node (ref "C17") (pin "2") (pinfunction "2_2") (pintype "passive"))
      (node (ref "C18") (pin "2") (pinfunction "2_2") (pintype "passive"))
      (node (ref "C19") (pin "2") (pinfunction "2_2") (pintype "passive"))
      (node (ref "C2") (pin "2") (pinfunction "2_2") (pintype "passive"))
      (node (ref "C20") (pin "-") (pinfunction "-_-") (pintype "passive"))
      (node (ref "C21") (pin "2") (pinfunction "2_2") (pintype "passive"))
      (node (ref "C22") (pin "2") (pinfunction "2_2") (pintype "passive"))
      (node (ref "C23") (pin "2") (pinfunction "2_2") (pintype "passive"))
      (node (ref "C24") (pin "2") (pinfunction "2_2") (pintype "passive"))
      (node (ref "C25") (pin "2") (pinfunction "2_2") (pintype "passive"))
      (node (ref "C26") (pin "2") (pinfunction "2_2") (pintype "passive"))
      (node (ref "C27") (pin "2") (pinfunction "2_2") (pintype "passive"))
      (node (ref "C28") (pin "2") (pinfunction "2_2") (pintype "passive"))
      (node (ref "C29") (pin "2") (pinfunction "2_2") (pintype "passive"))
      (node (ref "C3") (pin "2") (pinfunction "2_2") (pintype "passive"))
      (node (ref "C30") (pin "2") (pinfunction "2_2") (pintype "passive"))
      (node (ref "C46") (pin "2") (pinfunction "2_2") (pintype "passive"))
      (node (ref "C47") (pin "2") (pinfunction "2_2") (pintype "passive"))
      (node (ref "C5") (pin "2") (pinfunction "2_2") (pintype "passive"))
      (node (ref "C6") (pin "2") (pinfunction "2_2") (pintype "passive"))
      (node (ref "C7") (pin "2") (pinfunction "2_2") (pintype "passive"))
      (node (ref "C9") (pin "2") (pinfunction "2_2") (pintype "passive"))
      (node (ref "D2") (pin "A") (pinfunction "A_A") (pintype "passive"))
      (node (ref "D3") (pin "A") (pinfunction "A_A") (pintype "passive"))
      (node (ref "D8") (pin "A") (pinfunction "A_A") (pintype "passive"))
      (node (ref "IC1") (pin "15") (pinfunction "GND_15") (pintype "power_in"))
      (node (ref "IC1") (pin "8") (pinfunction "GND_8") (pintype "power_in"))
      (node (ref "IC1") (pin "PP") (pinfunction "GND_PP") (pintype "power_in"))
      (node (ref "IC16") (pin "2") (pinfunction "GND_2") (pintype "power_in"))
      (node (ref "IC2") (pin "16") (pinfunction "SYNC_16") (pintype "input"))
      (node (ref "IC2") (pin "PP") (pinfunction "GND_PP") (pintype "power_in"))
      (node (ref "IC3") (pin "3") (pinfunction "GND_3") (pintype "power_in"))
      (node (ref "J3") (pin "1") (pinfunction "1_1") (pintype "bidirectional"))
      (node (ref "J3") (pin "2") (pinfunction "2_2") (pintype "bidirectional"))
      (node (ref "J4") (pin "1") (pinfunction "1_1") (pintype "passive"))
      (node (ref "J4") (pin "3") (pinfunction "3_3") (pintype "passive"))
      (node (ref "J4") (pin "5") (pinfunction "5_5") (pintype "passive"))
      (node (ref "J5") (pin "1") (pinfunction "1_1") (pintype "bidirectional"))
      (node (ref "J7") (pin "1") (pinfunction "1_1") (pintype "bidirectional"))
      (node (ref "PCB1") (pin "P$14") (pinfunction "GND_P$14") (pintype "bidirectional"))
      (node (ref "PCB1") (pin "P$20") (pinfunction "GND_P$20") (pintype "bidirectional"))
      (node (ref "PCB1") (pin "P$25") (pinfunction "GND_P$25") (pintype "bidirectional"))
      (node (ref "PCB1") (pin "P$30") (pinfunction "GND_P$30") (pintype "bidirectional"))
      (node (ref "PCB1") (pin "P$34") (pinfunction "GND_P$34") (pintype "bidirectional"))
      (node (ref "PCB1") (pin "P$39") (pinfunction "GND_P$39") (pintype "bidirectional"))
      (node (ref "PCB1") (pin "P$6") (pinfunction "GND_P$6") (pintype "bidirectional"))
      (node (ref "PCB1") (pin "P$9") (pinfunction "GND_P$9") (pintype "bidirectional"))
      (node (ref "R12") (pin "1") (pinfunction "1_1") (pintype "passive"))
      (node (ref "R15") (pin "1") (pinfunction "1_1") (pintype "passive"))
      (node (ref "R16") (pin "1") (pinfunction "1_1") (pintype "passive"))
      (node (ref "R20") (pin "1") (pinfunction "1_1") (pintype "passive"))
      (node (ref "R4") (pin "2") (pinfunction "2_2") (pintype "passive"))
      (node (ref "R5") (pin "1") (pinfunction "1_1") (pintype "passive"))
      (node (ref "R51") (pin "1") (pinfunction "1_1") (pintype "passive"))
      (node (ref "R6") (pin "1") (pinfunction "1_1") (pintype "passive"))
      (node (ref "R7") (pin "1") (pinfunction "1_1") (pintype "passive"))
      (node (ref "R9") (pin "1") (pinfunction "1_1") (pintype "passive"))
      (node (ref "T1") (pin "2") (pinfunction "S_2") (pintype "passive"))
      (node (ref "U1") (pin "1") (pinfunction "A0_1") (pintype "bidirectional"))
      (node (ref "U1") (pin "14") (pinfunction "GND_14") (pintype "power_in"))
      (node (ref "U1") (pin "2") (pinfunction "A1_2") (pintype "bidirectional"))
      (node (ref "U1") (pin "24") (pinfunction "A5_24") (pintype "bidirectional"))
      (node (ref "U1") (pin "25") (pinfunction "EXTCLK_25") (pintype "input"))
      (node (ref "U1") (pin "3") (pinfunction "A2_3") (pintype "bidirectional"))
      (node (ref "U1") (pin "4") (pinfunction "A3_4") (pintype "bidirectional"))
      (node (ref "U1") (pin "5") (pinfunction "A4_5") (pintype "bidirectional"))
      (node (ref "U6") (pin "14") (pinfunction "RES_14") (pintype "bidirectional"))
      (node (ref "U6") (pin "15") (pinfunction "RES_15") (pintype "bidirectional"))
      (node (ref "U6") (pin "16") (pinfunction "RES_16") (pintype "bidirectional"))
      (node (ref "U6") (pin "17") (pinfunction "RES_17") (pintype "bidirectional"))
      (node (ref "U6") (pin "18") (pinfunction "RES_18") (pintype "bidirectional"))
      (node (ref "U6") (pin "19") (pinfunction "GND_19") (pintype "bidirectional"))
      (node (ref "U6") (pin "20") (pinfunction "GND_20") (pintype "bidirectional"))
    )
    (net (code "13") (name "GNDIO") (class "Default")
      (node (ref "D5") (pin "C") (pinfunction "C_C") (pintype "passive"))
      (node (ref "J1") (pin "1") (pinfunction "1_1") (pintype "passive"))
      (node (ref "J1") (pin "3") (pinfunction "3_3") (pintype "passive"))
      (node (ref "J1") (pin "5") (pinfunction "5_5") (pintype "passive"))
      (node (ref "Q1") (pin "3") (pinfunction "D_3") (pintype "passive"))
      (node (ref "R4") (pin "1") (pinfunction "1_1") (pintype "passive"))
    )
    (net (code "14") (name "INT1") (class "Default")
      (node (ref "PCB1") (pin "P$23") (pinfunction "GPIO11_P$23") (pintype "bidirectional"))
      (node (ref "R25") (pin "2") (pinfunction "2_2") (pintype "passive"))
    )
    (net (code "15") (name "INT2") (class "Default")
      (node (ref "PCB1") (pin "P$21") (pinfunction "GPIO9_P$21") (pintype "bidirectional"))
      (node (ref "R26") (pin "2") (pinfunction "2_2") (pintype "passive"))
    )
    (net (code "16") (name "INT_M") (class "Default")
      (node (ref "PCB1") (pin "P$29") (pinfunction "GPIO5_P$29") (pintype "bidirectional"))
      (node (ref "R29") (pin "2") (pinfunction "2_2") (pintype "passive"))
    )
    (net (code "17") (name "Net-(C9-Pad1)") (class "Default")
      (node (ref "C9") (pin "1") (pinfunction "1_1") (pintype "passive"))
      (node (ref "R10") (pin "1") (pinfunction "1_1") (pintype "passive"))
    )
    (net (code "18") (name "Net-(C13-Pad1)") (class "Default")
      (node (ref "C13") (pin "1") (pinfunction "1_1") (pintype "passive"))
      (node (ref "J6") (pin "2") (pinfunction "2_2") (pintype "bidirectional"))
      (node (ref "J6") (pin "4") (pinfunction "4_4") (pintype "bidirectional"))
      (node (ref "X2") (pin "1") (pinfunction "1_1") (pintype "passive"))
    )
    (net (code "19") (name "Net-(C17-Pad1)") (class "Default")
      (node (ref "C17") (pin "1") (pinfunction "1_1") (pintype "passive"))
      (node (ref "J5") (pin "3") (pinfunction "3_3") (pintype "bidirectional"))
      (node (ref "X3") (pin "1") (pinfunction "1_1") (pintype "passive"))
    )
    (net (code "20") (name "Net-(D1-A)") (class "Default")
      (node (ref "D1") (pin "1") (pinfunction "A_1") (pintype "passive"))
      (node (ref "D5") (pin "A") (pinfunction "A_A") (pintype "passive"))
      (node (ref "PAD2") (pin "P$1") (pinfunction "P_P$1") (pintype "passive"))
      (node (ref "Q1") (pin "2") (pinfunction "S_2") (pintype "passive"))
      (node (ref "R1") (pin "1") (pinfunction "1_1") (pintype "passive"))
    )
    (net (code "21") (name "Net-(D1-K)") (class "Default")
      (node (ref "D1") (pin "3") (pinfunction "K_3") (pintype "passive"))
      (node (ref "Q1") (pin "1") (pinfunction "G_1") (pintype "passive"))
      (node (ref "R1") (pin "2") (pinfunction "2_2") (pintype "passive"))
      (node (ref "R3") (pin "2") (pinfunction "2_2") (pintype "passive"))
    )
    (net (code "22") (name "Net-(D4-PadA)") (class "Default")
      (node (ref "D4") (pin "A") (pinfunction "A_A") (pintype "passive"))
      (node (ref "R18") (pin "1") (pinfunction "1_1") (pintype "passive"))
    )
    (net (code "23") (name "Net-(D8-C)") (class "Default")
      (node (ref "D8") (pin "K") (pinfunction "C_K") (pintype "passive"))
      (node (ref "IC1") (pin "3") (pinfunction "LED_3") (pintype "output"))
      (node (ref "J7") (pin "2") (pinfunction "2_2") (pintype "bidirectional"))
    )
    (net (code "24") (name "Net-(F1-1)") (class "Default")
      (node (ref "C22") (pin "1") (pinfunction "1_1") (pintype "passive"))
      (node (ref "F1") (pin "P$1") (pinfunction "1_P$1") (pintype "passive"))
      (node (ref "J3") (pin "3") (pinfunction "3_3") (pintype "bidirectional"))
      (node (ref "J3") (pin "4") (pinfunction "4_4") (pintype "bidirectional"))
    )
    (net (code "25") (name "Net-(IC1-BIAS)") (class "Default")
      (node (ref "C3") (pin "1") (pinfunction "1_1") (pintype "passive"))
      (node (ref "IC1") (pin "2") (pinfunction "OUT_2") (pintype "passive"))
      (node (ref "IC1") (pin "7") (pinfunction "BIAS_7") (pintype "passive"))
      (node (ref "L1") (pin "P$2") (pinfunction "2_P$2") (pintype "passive"))
    )
    (net (code "26") (name "Net-(IC1-BOOST)") (class "Default")
      (node (ref "C4") (pin "1") (pinfunction "1_1") (pintype "passive"))
      (node (ref "IC1") (pin "6") (pinfunction "BOOST_6") (pintype "passive"))
    )
    (net (code "27") (name "Net-(IC1-RT)") (class "Default")
      (node (ref "IC1") (pin "9") (pinfunction "RT_9") (pintype "passive"))
      (node (ref "R6") (pin "2") (pinfunction "2_2") (pintype "passive"))
    )
    (net (code "28") (name "Net-(IC1-SW)") (class "Default")
      (node (ref "C4") (pin "2") (pinfunction "2_2") (pintype "passive"))
      (node (ref "D2") (pin "C") (pinfunction "C_C") (pintype "passive"))
      (node (ref "IC1") (pin "5") (pinfunction "SW_5") (pintype "passive"))
      (node (ref "L1") (pin "P$1") (pinfunction "1_P$1") (pintype "passive"))
    )
    (net (code "29") (name "Net-(IC1-VADJ)") (class "Default")
      (node (ref "C5") (pin "1") (pinfunction "1_1") (pintype "passive"))
      (node (ref "IC1") (pin "13") (pinfunction "VADJ_13") (pintype "input"))
      (node (ref "R7") (pin "2") (pinfunction "2_2") (pintype "passive"))
      (node (ref "R8") (pin "2") (pinfunction "2_2") (pintype "passive"))
    )
    (net (code "30") (name "Net-(IC1-VC)") (class "Default")
      (node (ref "C2") (pin "1") (pinfunction "1_1") (pintype "passive"))
      (node (ref "IC1") (pin "12") (pinfunction "VC_12") (pintype "passive"))
    )
    (net (code "31") (name "Net-(IC1-~{SHDN})") (class "Default")
      (node (ref "C23") (pin "1") (pinfunction "1_1") (pintype "passive"))
      (node (ref "D4") (pin "K") (pinfunction "K_K") (pintype "passive"))
      (node (ref "IC1") (pin "10") (pinfunction "~{SHDN}_10") (pintype "input"))
      (node (ref "R5") (pin "2") (pinfunction "2_2") (pintype "passive"))
    )
    (net (code "32") (name "Net-(IC2-BOOST)") (class "Default")
      (node (ref "C8") (pin "1") (pinfunction "1_1") (pintype "passive"))
      (node (ref "IC2") (pin "4") (pinfunction "BOOST_4") (pintype "passive"))
    )
    (net (code "33") (name "Net-(IC2-FB)") (class "Default")
      (node (ref "C10") (pin "2") (pinfunction "2_2") (pintype "passive"))
      (node (ref "IC2") (pin "1") (pinfunction "FB_1") (pintype "input"))
      (node (ref "R11") (pin "1") (pinfunction "1_1") (pintype "passive"))
      (node (ref "R12") (pin "2") (pinfunction "2_2") (pintype "passive"))
    )
    (net (code "34") (name "Net-(IC2-RT)") (class "Default")
      (node (ref "IC2") (pin "14") (pinfunction "RT_14") (pintype "passive"))
      (node (ref "R9") (pin "2") (pinfunction "2_2") (pintype "passive"))
    )
    (net (code "35") (name "Net-(IC2-SS)") (class "Default")
      (node (ref "C7") (pin "1") (pinfunction "1_1") (pintype "passive"))
      (node (ref "IC2") (pin "2") (pinfunction "SS_2") (pintype "passive"))
    )
    (net (code "36") (name "Net-(IC3-ADDR)") (class "Default")
      (node (ref "IC3") (pin "1") (pinfunction "ADDR_1") (pintype "input"))
      (node (ref "R51") (pin "2") (pinfunction "2_2") (pintype "passive"))
    )
    (net (code "37") (name "Net-(IC3-IN0)") (class "Default")
      (node (ref "C15") (pin "1") (pinfunction "1_1") (pintype "passive"))
      (node (ref "IC3") (pin "4") (pinfunction "IN0_4") (pintype "input"))
      (node (ref "J6") (pin "1") (pinfunction "1_1") (pintype "bidirectional"))
      (node (ref "R15") (pin "2") (pinfunction "2_2") (pintype "passive"))
    )
    (net (code "38") (name "Net-(IC3-IN1)") (class "Default")
      (node (ref "C18") (pin "1") (pinfunction "1_1") (pintype "passive"))
      (node (ref "IC3") (pin "5") (pinfunction "IN1_5") (pintype "input"))
      (node (ref "R17") (pin "2") (pinfunction "2_2") (pintype "passive"))
    )
    (net (code "39") (name "Net-(IC3-IN2)") (class "Default")
      (node (ref "C16") (pin "1") (pinfunction "1_1") (pintype "passive"))
      (node (ref "IC3") (pin "6") (pinfunction "IN2_6") (pintype "input"))
      (node (ref "J6") (pin "3") (pinfunction "3_3") (pintype "bidirectional"))
      (node (ref "R16") (pin "2") (pinfunction "2_2") (pintype "passive"))
    )
    (net (code "40") (name "Net-(IC3-VDD)") (class "Default")
      (node (ref "C12") (pin "1") (pinfunction "1_1") (pintype "passive"))
      (node (ref "IC3") (pin "8") (pinfunction "VDD_8") (pintype "power_in"))
      (node (ref "X1") (pin "1") (pinfunction "1_1") (pintype "passive"))
    )
    (net (code "41") (name "Net-(J2-Pad1)") (class "Default")
      (node (ref "J2") (pin "1") (pinfunction "1_1") (pintype "bidirectional"))
      (node (ref "R2") (pin "1") (pinfunction "1_1") (pintype "passive"))
    )
    (net (code "42") (name "Net-(J2-Pad2)") (class "Default")
      (node (ref "J2") (pin "2") (pinfunction "2_2") (pintype "bidirectional"))
      (node (ref "R3") (pin "1") (pinfunction "1_1") (pintype "passive"))
    )
    (net (code "43") (name "Net-(J4-Pad2)") (class "Default")
      (node (ref "J4") (pin "2") (pinfunction "2_2") (pintype "passive"))
      (node (ref "R24") (pin "2") (pinfunction "2_2") (pintype "passive"))
    )
    (net (code "44") (name "Net-(J4-Pad4)") (class "Default")
      (node (ref "J4") (pin "4") (pinfunction "4_4") (pintype "passive"))
      (node (ref "R23") (pin "2") (pinfunction "2_2") (pintype "passive"))
    )
    (net (code "45") (name "Net-(J4-Pad6)") (class "Default")
      (node (ref "J4") (pin "6") (pinfunction "6_6") (pintype "passive"))
      (node (ref "R22") (pin "2") (pinfunction "2_2") (pintype "passive"))
    )
    (net (code "46") (name "Net-(J5-Pad2)") (class "Default")
      (node (ref "J5") (pin "2") (pinfunction "2_2") (pintype "bidirectional"))
      (node (ref "R17") (pin "1") (pinfunction "1_1") (pintype "passive"))
    )
    (net (code "47") (name "Net-(L2-1)") (class "Default")
      (node (ref "C8") (pin "2") (pinfunction "2_2") (pintype "passive"))
      (node (ref "D3") (pin "C") (pinfunction "C_C") (pintype "passive"))
      (node (ref "IC2") (pin "5") (pinfunction "SW_5") (pintype "passive"))
      (node (ref "IC2") (pin "6") (pinfunction "SW_6") (pintype "passive"))
      (node (ref "IC2") (pin "7") (pinfunction "SW_7") (pintype "passive"))
      (node (ref "L2") (pin "P$1") (pinfunction "1_P$1") (pintype "passive"))
      (node (ref "R10") (pin "2") (pinfunction "2_2") (pintype "passive"))
    )
    (net (code "48") (name "Net-(PAD1-P)") (class "Default")
      (node (ref "D6") (pin "A") (pinfunction "A_A") (pintype "passive"))
      (node (ref "J1") (pin "2") (pinfunction "2_2") (pintype "passive"))
      (node (ref "J1") (pin "4") (pinfunction "4_4") (pintype "passive"))
      (node (ref "J1") (pin "6") (pinfunction "6_6") (pintype "passive"))
      (node (ref "PAD1") (pin "P$1") (pinfunction "P_P$1") (pintype "passive"))
      (node (ref "R19") (pin "2") (pinfunction "2_2") (pintype "passive"))
      (node (ref "R2") (pin "2") (pinfunction "2_2") (pintype "passive"))
    )
    (net (code "49") (name "Net-(T1-D)") (class "Default")
      (node (ref "R21") (pin "1") (pinfunction "1_1") (pintype "passive"))
      (node (ref "T1") (pin "3") (pinfunction "D_3") (pintype "passive"))
      (node (ref "U1") (pin "23") (pinfunction "#OE_23") (pintype "input"))
    )
    (net (code "50") (name "Net-(T1-G)") (class "Default")
      (node (ref "R31") (pin "1") (pinfunction "1_1") (pintype "passive"))
      (node (ref "T1") (pin "1") (pinfunction "G_1") (pintype "passive"))
    )
    (net (code "51") (name "Net-(U1-PWM0)") (class "Default")
      (node (ref "R22") (pin "1") (pinfunction "1_1") (pintype "passive"))
      (node (ref "U1") (pin "6") (pinfunction "PWM0_6") (pintype "output"))
    )
    (net (code "52") (name "Net-(U1-PWM1)") (class "Default")
      (node (ref "R23") (pin "1") (pinfunction "1_1") (pintype "passive"))
      (node (ref "U1") (pin "7") (pinfunction "PWM1_7") (pintype "output"))
    )
    (net (code "53") (name "Net-(U1-PWM2)") (class "Default")
      (node (ref "R24") (pin "1") (pinfunction "1_1") (pintype "passive"))
      (node (ref "U1") (pin "8") (pinfunction "PWM2_8") (pintype "output"))
    )
    (net (code "54") (name "Net-(U1-PWM3)") (class "Default")
      (node (ref "R18") (pin "2") (pinfunction "2_2") (pintype "passive"))
      (node (ref "R8") (pin "1") (pinfunction "1_1") (pintype "passive"))
      (node (ref "U1") (pin "9") (pinfunction "PWM3_9") (pintype "output"))
    )
    (net (code "55") (name "Net-(U6-C1)") (class "Default")
      (node (ref "C24") (pin "1") (pinfunction "1_1") (pintype "passive"))
      (node (ref "U6") (pin "24") (pinfunction "C1_24") (pintype "bidirectional"))
    )
    (net (code "56") (name "Net-(U6-CAP)") (class "Default")
      (node (ref "C25") (pin "1") (pinfunction "1_1") (pintype "passive"))
      (node (ref "U6") (pin "21") (pinfunction "CAP_21") (pintype "bidirectional"))
    )
    (net (code "57") (name "Net-(U6-DEN_A{slash}G)") (class "Default")
      (node (ref "R27") (pin "1") (pinfunction "1_1") (pintype "passive"))
      (node (ref "U6") (pin "13") (pinfunction "DEN_A/G_13") (pintype "bidirectional"))
    )
    (net (code "58") (name "Net-(U6-DRDY_M)") (class "Default")
      (node (ref "R28") (pin "1") (pinfunction "1_1") (pintype "passive"))
      (node (ref "U6") (pin "9") (pinfunction "DRDY_M_9") (pintype "bidirectional"))
    )
    (net (code "59") (name "Net-(U6-INT1_A{slash}G)") (class "Default")
      (node (ref "R25") (pin "1") (pinfunction "1_1") (pintype "passive"))
      (node (ref "U6") (pin "11") (pinfunction "INT1_A/G_11") (pintype "bidirectional"))
    )
    (net (code "60") (name "Net-(U6-INT2_A{slash}G)") (class "Default")
      (node (ref "R26") (pin "1") (pinfunction "1_1") (pintype "passive"))
      (node (ref "U6") (pin "12") (pinfunction "INT2_A/G_12") (pintype "bidirectional"))
    )
    (net (code "61") (name "Net-(U6-INT_M)") (class "Default")
      (node (ref "R29") (pin "1") (pinfunction "1_1") (pintype "passive"))
      (node (ref "U6") (pin "10") (pinfunction "INT_M_10") (pintype "bidirectional"))
    )
    (net (code "62") (name "VCC") (class "Default")
      (node (ref "C1") (pin "1") (pinfunction "1_1") (pintype "passive"))
      (node (ref "C14") (pin "+") (pinfunction "+_+") (pintype "passive"))
      (node (ref "C29") (pin "1") (pinfunction "1_1") (pintype "passive"))
      (node (ref "C6") (pin "1") (pinfunction "1_1") (pintype "passive"))
      (node (ref "D6") (pin "C") (pinfunction "C_C") (pintype "passive"))
      (node (ref "F1") (pin "P$2") (pinfunction "2_P$2") (pintype "passive"))
      (node (ref "IC1") (pin "4") (pinfunction "VIN_4") (pintype "power_in"))
      (node (ref "IC2") (pin "10") (pinfunction "VIN_10") (pintype "power_in"))
      (node (ref "IC2") (pin "11") (pinfunction "VIN_11") (pintype "power_in"))
      (node (ref "IC2") (pin "12") (pinfunction "VIN_12") (pintype "power_in"))
      (node (ref "IC2") (pin "13") (pinfunction "EN_13") (pintype "input"))
    )
    (net (code "63") (name "unconnected-(IC1-PWM-Pad14)") (class "Default")
      (node (ref "IC1") (pin "14") (pinfunction "PWM_14") (pintype "input"))
    )
    (net (code "64") (name "unconnected-(IC1-REF-Pad11)") (class "Default")
      (node (ref "IC1") (pin "11") (pinfunction "REF_11") (pintype "passive"))
    )
    (net (code "65") (name "unconnected-(IC2-PG-Pad15)") (class "Default")
      (node (ref "IC2") (pin "15") (pinfunction "PG_15") (pintype "output"))
    )
    (net (code "66") (name "unconnected-(PCB1-GPIO4-PadP$7)") (class "Default")
      (node (ref "PCB1") (pin "P$7") (pinfunction "GPIO4_P$7") (pintype "bidirectional"))
    )
    (net (code "67") (name "unconnected-(PCB1-GPIO7-PadP$26)") (class "Default")
      (node (ref "PCB1") (pin "P$26") (pinfunction "GPIO7_P$26") (pintype "bidirectional"))
    )
    (net (code "68") (name "unconnected-(PCB1-GPIO8-PadP$24)") (class "Default")
      (node (ref "PCB1") (pin "P$24") (pinfunction "GPIO8_P$24") (pintype "bidirectional"))
    )
    (net (code "69") (name "unconnected-(PCB1-GPIO12-PadP$32)") (class "Default")
      (node (ref "PCB1") (pin "P$32") (pinfunction "GPIO12_P$32") (pintype "bidirectional"))
    )
    (net (code "70") (name "unconnected-(PCB1-GPIO14-PadP$8)") (class "Default")
      (node (ref "PCB1") (pin "P$8") (pinfunction "GPIO14_P$8") (pintype "bidirectional"))
    )
    (net (code "71") (name "unconnected-(PCB1-GPIO15-PadP$10)") (class "Default")
      (node (ref "PCB1") (pin "P$10") (pinfunction "GPIO15_P$10") (pintype "bidirectional"))
    )
    (net (code "72") (name "unconnected-(PCB1-GPIO16-PadP$36)") (class "Default")
      (node (ref "PCB1") (pin "P$36") (pinfunction "GPIO16_P$36") (pintype "bidirectional"))
    )
    (net (code "73") (name "unconnected-(PCB1-GPIO17-PadP$11)") (class "Default")
      (node (ref "PCB1") (pin "P$11") (pinfunction "GPIO17_P$11") (pintype "bidirectional"))
    )
    (net (code "74") (name "unconnected-(PCB1-GPIO18-PadP$12)") (class "Default")
      (node (ref "PCB1") (pin "P$12") (pinfunction "GPIO18_P$12") (pintype "bidirectional"))
    )
    (net (code "75") (name "unconnected-(PCB1-GPIO19-PadP$35)") (class "Default")
      (node (ref "PCB1") (pin "P$35") (pinfunction "GPIO19_P$35") (pintype "bidirectional"))
    )
    (net (code "76") (name "unconnected-(PCB1-GPIO21-PadP$40)") (class "Default")
      (node (ref "PCB1") (pin "P$40") (pinfunction "GPIO21_P$40") (pintype "bidirectional"))
    )
    (net (code "77") (name "unconnected-(PCB1-GPIO22-PadP$15)") (class "Default")
      (node (ref "PCB1") (pin "P$15") (pinfunction "GPIO22_P$15") (pintype "bidirectional"))
    )
    (net (code "78") (name "unconnected-(PCB1-GPIO23-PadP$16)") (class "Default")
      (node (ref "PCB1") (pin "P$16") (pinfunction "GPIO23_P$16") (pintype "bidirectional"))
    )
    (net (code "79") (name "unconnected-(PCB1-GPIO24-PadP$18)") (class "Default")
      (node (ref "PCB1") (pin "P$18") (pinfunction "GPIO24_P$18") (pintype "bidirectional"))
    )
    (net (code "80") (name "unconnected-(PCB1-GPIO25-PadP$22)") (class "Default")
      (node (ref "PCB1") (pin "P$22") (pinfunction "GPIO25_P$22") (pintype "bidirectional"))
    )
    (net (code "81") (name "unconnected-(PCB1-GPIO26-PadP$37)") (class "Default")
      (node (ref "PCB1") (pin "P$37") (pinfunction "GPIO26_P$37") (pintype "bidirectional"))
    )
    (net (code "82") (name "unconnected-(PCB1-GPIO27-PadP$13)") (class "Default")
      (node (ref "PCB1") (pin "P$13") (pinfunction "GPIO27_P$13") (pintype "bidirectional"))
    )
    (net (code "83") (name "unconnected-(PCB1-RSVD1-PadP$27)") (class "Default")
      (node (ref "PCB1") (pin "P$27") (pinfunction "RSVD1_P$27") (pintype "bidirectional"))
    )
    (net (code "84") (name "unconnected-(PCB1-RSVD2-PadP$28)") (class "Default")
      (node (ref "PCB1") (pin "P$28") (pinfunction "RSVD2_P$28") (pintype "bidirectional"))
    )
    (net (code "85") (name "unconnected-(U1-PWM4-Pad10)") (class "Default")
      (node (ref "U1") (pin "10") (pinfunction "PWM4_10") (pintype "output"))
    )
    (net (code "86") (name "unconnected-(U1-PWM5-Pad11)") (class "Default")
      (node (ref "U1") (pin "11") (pinfunction "PWM5_11") (pintype "output"))
    )
    (net (code "87") (name "unconnected-(U1-PWM6-Pad12)") (class "Default")
      (node (ref "U1") (pin "12") (pinfunction "PWM6_12") (pintype "output"))
    )
    (net (code "88") (name "unconnected-(U1-PWM7-Pad13)") (class "Default")
      (node (ref "U1") (pin "13") (pinfunction "PWM7_13") (pintype "output"))
    )
    (net (code "89") (name "unconnected-(U1-PWM8-Pad15)") (class "Default")
      (node (ref "U1") (pin "15") (pinfunction "PWM8_15") (pintype "output"))
    )
    (net (code "90") (name "unconnected-(U1-PWM9-Pad16)") (class "Default")
      (node (ref "U1") (pin "16") (pinfunction "PWM9_16") (pintype "output"))
    )
    (net (code "91") (name "unconnected-(U1-PWM10-Pad17)") (class "Default")
      (node (ref "U1") (pin "17") (pinfunction "PWM10_17") (pintype "output"))
    )
    (net (code "92") (name "unconnected-(U1-PWM11-Pad18)") (class "Default")
      (node (ref "U1") (pin "18") (pinfunction "PWM11_18") (pintype "output"))
    )
    (net (code "93") (name "unconnected-(U1-PWM12-Pad19)") (class "Default")
      (node (ref "U1") (pin "19") (pinfunction "PWM12_19") (pintype "output"))
    )
    (net (code "94") (name "unconnected-(U1-PWM13-Pad20)") (class "Default")
      (node (ref "U1") (pin "20") (pinfunction "PWM13_20") (pintype "output"))
    )
    (net (code "95") (name "unconnected-(U1-PWM14-Pad21)") (class "Default")
      (node (ref "U1") (pin "21") (pinfunction "PWM14_21") (pintype "output"))
    )
    (net (code "96") (name "unconnected-(U1-PWM15-Pad22)") (class "Default")
      (node (ref "U1") (pin "22") (pinfunction "PWM15_22") (pintype "output"))
    )
  )
)
